# nokia-phone-arduino-shield.net
KiCad netlist of a schematic drawn in EAGLE
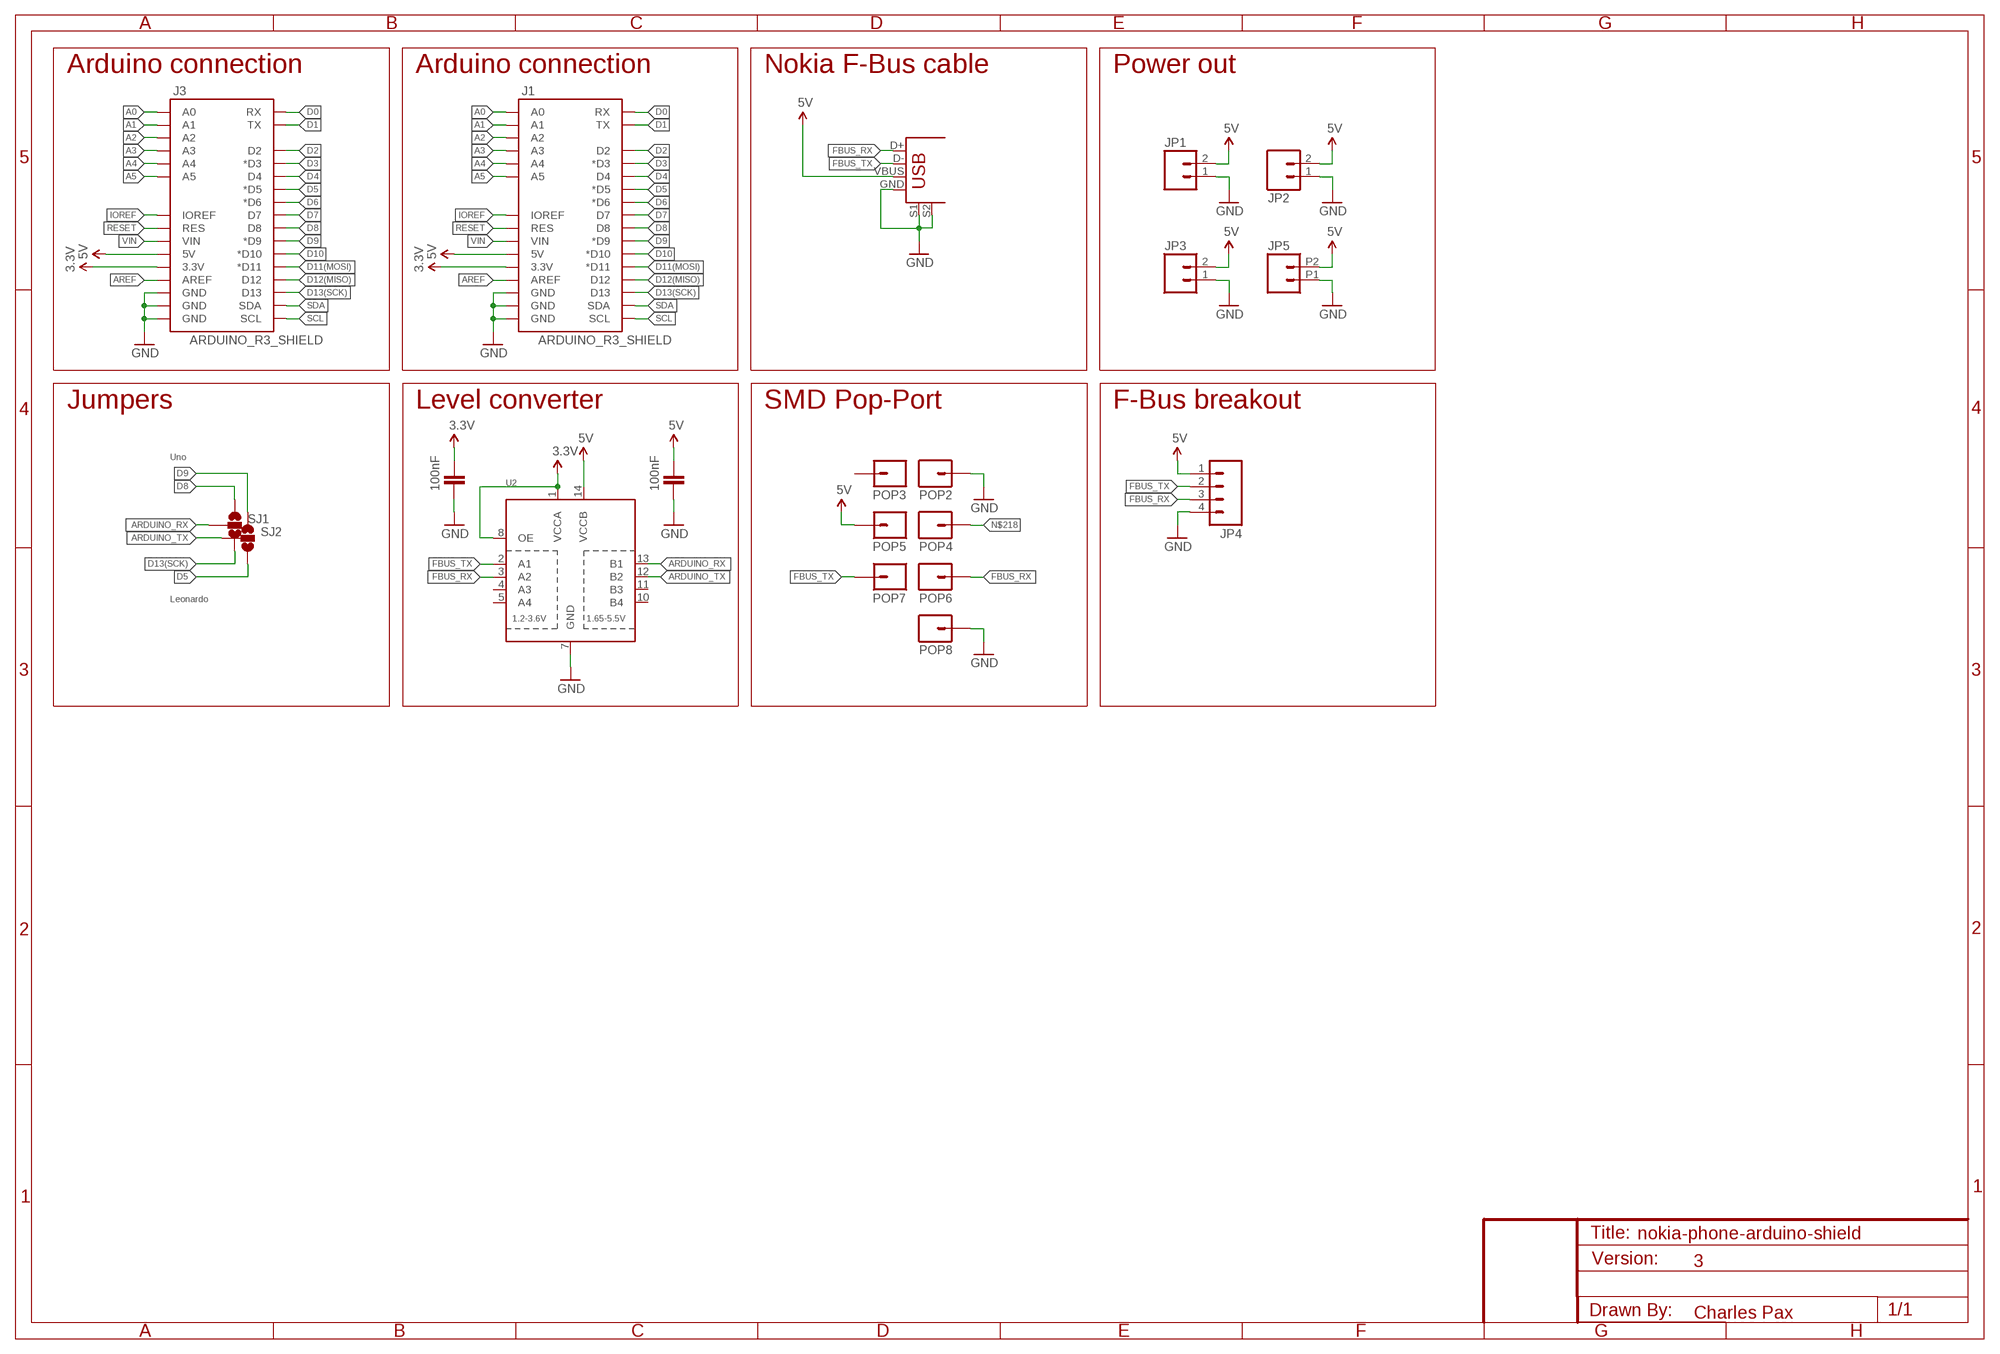
[diagram p0: schematic, sheet 1]

(export (version "E")
  (design (tool "Eeschema 10.0.6"))
  (components
    (comp (ref "C3")
      (value "100nF")
      (footprint "eagle-import:SPARKFUN-CAPACITORS_0603-CAP")
      (fields (field (name "MPN") "CL10B104KO8NNNC"))
      (libsource (lib "eagle-import") (part "SPARKFUN-CAPACITORS_CAP0603-CAP"))
    )
    (comp (ref "C4")
      (value "100nF")
      (footprint "eagle-import:SPARKFUN-CAPACITORS_0603-CAP")
      (fields (field (name "MPN") "CL10B104KO8NNNC"))
      (libsource (lib "eagle-import") (part "SPARKFUN-CAPACITORS_CAP0603-CAP"))
    )
    (comp (ref "J1")
      (value "ARDUINO_R3_SHIELD")
      (footprint "eagle-import:UNO_R3_SHIELD_NOLABELS_LOCK")
      (libsource (lib "eagle-import") (part "ARDUINO_R3_SHIELDUNO_R3_SHIELD_NOLABELS_LOCK"))
    )
    (comp (ref "J3")
      (value "ARDUINO_R3_SHIELD")
      (footprint "eagle-import:UNO_R3_SHIELD_NOLABELS_LOCK")
      (libsource (lib "eagle-import") (part "ARDUINO_R3_SHIELDUNO_R3_SHIELD_NOLABELS_LOCK"))
    )
    (comp (ref "JP1")
      (value "M02LOCK")
      (footprint "eagle-import:1X02_LOCK")
      (libsource (lib "eagle-import") (part "M02LOCK"))
    )
    (comp (ref "JP2")
      (value "M02-JST-2MM-SMT")
      (footprint "eagle-import:JST-2-SMD")
      (libsource (lib "eagle-import") (part "M02-JST-2MM-SMT"))
    )
    (comp (ref "JP3")
      (value "M02LOCK")
      (footprint "eagle-import:1X02_LOCK")
      (libsource (lib "eagle-import") (part "M02LOCK"))
    )
    (comp (ref "JP4")
      (value "M04LOCK")
      (footprint "eagle-import:1X04_LOCK")
      (libsource (lib "eagle-import") (part "M04LOCK"))
    )
    (comp (ref "JP5")
      (value "M022.54MM_SCREWTERM")
      (footprint "eagle-import:1X02_2.54_SCREWTERM")
      (libsource (lib "eagle-import") (part "M022.54MM_SCREWTERM"))
    )
    (comp (ref "POP2")
      (value "M01SMD-4.5X1.5")
      (footprint "eagle-import:PAD-1.5X4.5")
      (libsource (lib "eagle-import") (part "M01SMD-4.5X1.5"))
    )
    (comp (ref "POP3")
      (value "M01SMD-4.5X1.5")
      (footprint "eagle-import:PAD-1.5X4.5")
      (libsource (lib "eagle-import") (part "M01SMD-4.5X1.5"))
    )
    (comp (ref "POP4")
      (value "M01SMD-4.5X1.5")
      (footprint "eagle-import:PAD-1.5X4.5")
      (libsource (lib "eagle-import") (part "M01SMD-4.5X1.5"))
    )
    (comp (ref "POP5")
      (value "M01SMD-4.5X1.5")
      (footprint "eagle-import:PAD-1.5X4.5")
      (libsource (lib "eagle-import") (part "M01SMD-4.5X1.5"))
    )
    (comp (ref "POP6")
      (value "M01SMD-4.5X1.5")
      (footprint "eagle-import:PAD-1.5X4.5")
      (libsource (lib "eagle-import") (part "M01SMD-4.5X1.5"))
    )
    (comp (ref "POP7")
      (value "M01SMD-4.5X1.5")
      (footprint "eagle-import:PAD-1.5X4.5")
      (libsource (lib "eagle-import") (part "M01SMD-4.5X1.5"))
    )
    (comp (ref "POP8")
      (value "M01SMD-4.5X1.5")
      (footprint "eagle-import:PAD-1.5X4.5")
      (libsource (lib "eagle-import") (part "M01SMD-4.5X1.5"))
    )
    (comp (ref "SJ1")
      (value "SOLDERJUMPER_2WAYS")
      (footprint "eagle-import:SJ_3")
      (libsource (lib "eagle-import") (part "SOLDERJUMPER_2WAYS"))
    )
    (comp (ref "SJ2")
      (value "SOLDERJUMPER_2WAYS")
      (footprint "eagle-import:SJ_3")
      (libsource (lib "eagle-import") (part "SOLDERJUMPER_2WAYS"))
    )
    (comp (ref "U$2")
      (value "USB+SHIELDUSB-A-S-NOSILK-FEMALE")
      (footprint "eagle-import:USB-A-S-NOSILK-FEMALE")
      (libsource (lib "eagle-import") (part "USB+SHIELDUSB-A-S-NOSILK-FEMALE"))
    )
    (comp (ref "U2")
      (value "TXB0104PWRSOIC14")
      (footprint "eagle-import:SO14")
      (fields (field (name "MPN") "TXB0104DR"))
      (libsource (lib "eagle-import") (part "TXB0104PWRSOIC14"))
    )
  )
  (nets
    (net (code "1") (name "3.3V") (class "Default")
      (node (ref "C3") (pin "2") (pinfunction "2_2") (pintype "passive"))
      (node (ref "J1") (pin "3.3V") (pinfunction "3.3V_3.3V") (pintype "bidirectional"))
      (node (ref "J3") (pin "3.3V") (pinfunction "3.3V_3.3V") (pintype "bidirectional"))
      (node (ref "U2") (pin "1") (pinfunction "VCCA_1") (pintype "bidirectional"))
      (node (ref "U2") (pin "8") (pinfunction "OE_8") (pintype "bidirectional"))
    )
    (net (code "2") (name "5V") (class "Default")
      (node (ref "C4") (pin "2") (pinfunction "2_2") (pintype "passive"))
      (node (ref "J1") (pin "5V") (pinfunction "5V_5V") (pintype "bidirectional"))
      (node (ref "J3") (pin "5V") (pinfunction "5V_5V") (pintype "bidirectional"))
      (node (ref "JP1") (pin "2") (pinfunction "2_2") (pintype "passive"))
      (node (ref "JP2") (pin "2") (pinfunction "1_2") (pintype "passive"))
      (node (ref "JP3") (pin "2") (pinfunction "2_2") (pintype "passive"))
      (node (ref "JP4") (pin "1") (pinfunction "1_1") (pintype "passive"))
      (node (ref "JP5") (pin "P2") (pinfunction "2_P2") (pintype "passive"))
      (node (ref "POP5") (pin "P$1") (pinfunction "1_P$1") (pintype "passive"))
      (node (ref "U$2") (pin "VBUS") (pinfunction "VBUS_VBUS") (pintype "bidirectional"))
      (node (ref "U2") (pin "14") (pinfunction "VCCB_14") (pintype "bidirectional"))
    )
    (net (code "3") (name "A0") (class "Default")
      (node (ref "J1") (pin "A0") (pinfunction "A0_A0") (pintype "bidirectional"))
      (node (ref "J3") (pin "A0") (pinfunction "A0_A0") (pintype "bidirectional"))
    )
    (net (code "4") (name "A1") (class "Default")
      (node (ref "J1") (pin "A1") (pinfunction "A1_A1") (pintype "bidirectional"))
      (node (ref "J3") (pin "A1") (pinfunction "A1_A1") (pintype "bidirectional"))
    )
    (net (code "5") (name "A2") (class "Default")
      (node (ref "J1") (pin "A2") (pinfunction "A2_A2") (pintype "bidirectional"))
      (node (ref "J3") (pin "A2") (pinfunction "A2_A2") (pintype "bidirectional"))
    )
    (net (code "6") (name "A3") (class "Default")
      (node (ref "J1") (pin "A3") (pinfunction "A3_A3") (pintype "bidirectional"))
      (node (ref "J3") (pin "A3") (pinfunction "A3_A3") (pintype "bidirectional"))
    )
    (net (code "7") (name "A4") (class "Default")
      (node (ref "J1") (pin "A4") (pinfunction "A4_A4") (pintype "bidirectional"))
      (node (ref "J3") (pin "A4") (pinfunction "A4_A4") (pintype "bidirectional"))
    )
    (net (code "8") (name "A5") (class "Default")
      (node (ref "J1") (pin "A5") (pinfunction "A5_A5") (pintype "bidirectional"))
      (node (ref "J3") (pin "A5") (pinfunction "A5_A5") (pintype "bidirectional"))
    )
    (net (code "9") (name "ARDUINO_RX") (class "Default")
      (node (ref "SJ1") (pin "2") (pinfunction "2_2") (pintype "passive"))
      (node (ref "U2") (pin "13") (pinfunction "B1_13") (pintype "bidirectional"))
    )
    (net (code "10") (name "ARDUINO_TX") (class "Default")
      (node (ref "SJ2") (pin "2") (pinfunction "2_2") (pintype "passive"))
      (node (ref "U2") (pin "12") (pinfunction "B2_12") (pintype "bidirectional"))
    )
    (net (code "11") (name "AREF") (class "Default")
      (node (ref "J1") (pin "AREF") (pinfunction "AREF_AREF") (pintype "bidirectional"))
      (node (ref "J3") (pin "AREF") (pinfunction "AREF_AREF") (pintype "bidirectional"))
    )
    (net (code "12") (name "D0") (class "Default")
      (node (ref "J1") (pin "RX") (pinfunction "RX_RX") (pintype "bidirectional"))
      (node (ref "J3") (pin "RX") (pinfunction "RX_RX") (pintype "bidirectional"))
    )
    (net (code "13") (name "D1") (class "Default")
      (node (ref "J1") (pin "TX") (pinfunction "TX_TX") (pintype "bidirectional"))
      (node (ref "J3") (pin "TX") (pinfunction "TX_TX") (pintype "bidirectional"))
    )
    (net (code "14") (name "D2") (class "Default")
      (node (ref "J1") (pin "D2") (pinfunction "D2_D2") (pintype "bidirectional"))
      (node (ref "J3") (pin "D2") (pinfunction "D2_D2") (pintype "bidirectional"))
    )
    (net (code "15") (name "D3") (class "Default")
      (node (ref "J1") (pin "D3") (pinfunction "*D3_D3") (pintype "bidirectional"))
      (node (ref "J3") (pin "D3") (pinfunction "*D3_D3") (pintype "bidirectional"))
    )
    (net (code "16") (name "D4") (class "Default")
      (node (ref "J1") (pin "D4") (pinfunction "D4_D4") (pintype "bidirectional"))
      (node (ref "J3") (pin "D4") (pinfunction "D4_D4") (pintype "bidirectional"))
    )
    (net (code "17") (name "D5") (class "Default")
      (node (ref "J1") (pin "D5") (pinfunction "*D5_D5") (pintype "bidirectional"))
      (node (ref "J3") (pin "D5") (pinfunction "*D5_D5") (pintype "bidirectional"))
      (node (ref "SJ2") (pin "3") (pinfunction "3_3") (pintype "passive"))
    )
    (net (code "18") (name "D6") (class "Default")
      (node (ref "J1") (pin "D6") (pinfunction "*D6_D6") (pintype "bidirectional"))
      (node (ref "J3") (pin "D6") (pinfunction "*D6_D6") (pintype "bidirectional"))
    )
    (net (code "19") (name "D7") (class "Default")
      (node (ref "J1") (pin "D7") (pinfunction "D7_D7") (pintype "bidirectional"))
      (node (ref "J3") (pin "D7") (pinfunction "D7_D7") (pintype "bidirectional"))
    )
    (net (code "20") (name "D8") (class "Default")
      (node (ref "J1") (pin "D8") (pinfunction "D8_D8") (pintype "bidirectional"))
      (node (ref "J3") (pin "D8") (pinfunction "D8_D8") (pintype "bidirectional"))
      (node (ref "SJ1") (pin "1") (pinfunction "1_1") (pintype "passive"))
    )
    (net (code "21") (name "D9") (class "Default")
      (node (ref "J1") (pin "D9") (pinfunction "*D9_D9") (pintype "bidirectional"))
      (node (ref "J3") (pin "D9") (pinfunction "*D9_D9") (pintype "bidirectional"))
      (node (ref "SJ2") (pin "1") (pinfunction "1_1") (pintype "passive"))
    )
    (net (code "22") (name "D10") (class "Default")
      (node (ref "J1") (pin "D10") (pinfunction "*D10_D10") (pintype "bidirectional"))
      (node (ref "J3") (pin "D10") (pinfunction "*D10_D10") (pintype "bidirectional"))
    )
    (net (code "23") (name "D11(MOSI)") (class "Default")
      (node (ref "J1") (pin "D11") (pinfunction "*D11_D11") (pintype "bidirectional"))
      (node (ref "J3") (pin "D11") (pinfunction "*D11_D11") (pintype "bidirectional"))
    )
    (net (code "24") (name "D12(MISO)") (class "Default")
      (node (ref "J1") (pin "D12") (pinfunction "D12_D12") (pintype "bidirectional"))
      (node (ref "J3") (pin "D12") (pinfunction "D12_D12") (pintype "bidirectional"))
    )
    (net (code "25") (name "D13(SCK)") (class "Default")
      (node (ref "J1") (pin "D13") (pinfunction "D13_D13") (pintype "bidirectional"))
      (node (ref "J3") (pin "D13") (pinfunction "D13_D13") (pintype "bidirectional"))
      (node (ref "SJ1") (pin "3") (pinfunction "3_3") (pintype "passive"))
    )
    (net (code "26") (name "FBUS_RX") (class "Default")
      (node (ref "JP4") (pin "3") (pinfunction "3_3") (pintype "passive"))
      (node (ref "POP6") (pin "P$1") (pinfunction "1_P$1") (pintype "passive"))
      (node (ref "U$2") (pin "D+") (pinfunction "D+_D+") (pintype "bidirectional"))
      (node (ref "U2") (pin "3") (pinfunction "A2_3") (pintype "bidirectional"))
    )
    (net (code "27") (name "FBUS_TX") (class "Default")
      (node (ref "JP4") (pin "2") (pinfunction "2_2") (pintype "passive"))
      (node (ref "POP7") (pin "P$1") (pinfunction "1_P$1") (pintype "passive"))
      (node (ref "U$2") (pin "D-") (pinfunction "D-_D-") (pintype "bidirectional"))
      (node (ref "U2") (pin "2") (pinfunction "A1_2") (pintype "bidirectional"))
    )
    (net (code "28") (name "GND") (class "Default")
      (node (ref "C3") (pin "1") (pinfunction "1_1") (pintype "passive"))
      (node (ref "C4") (pin "1") (pinfunction "1_1") (pintype "passive"))
      (node (ref "J1") (pin "GND@0") (pinfunction "GND_GND@0") (pintype "bidirectional"))
      (node (ref "J1") (pin "GND@1") (pinfunction "GND_GND@1") (pintype "bidirectional"))
      (node (ref "J1") (pin "GND@2") (pinfunction "GND_GND@2") (pintype "bidirectional"))
      (node (ref "J3") (pin "GND@0") (pinfunction "GND_GND@0") (pintype "bidirectional"))
      (node (ref "J3") (pin "GND@1") (pinfunction "GND_GND@1") (pintype "bidirectional"))
      (node (ref "J3") (pin "GND@2") (pinfunction "GND_GND@2") (pintype "bidirectional"))
      (node (ref "JP1") (pin "1") (pinfunction "1_1") (pintype "passive"))
      (node (ref "JP2") (pin "1") (pinfunction "2_1") (pintype "passive"))
      (node (ref "JP3") (pin "1") (pinfunction "1_1") (pintype "passive"))
      (node (ref "JP4") (pin "4") (pinfunction "4_4") (pintype "passive"))
      (node (ref "JP5") (pin "P1") (pinfunction "1_P1") (pintype "passive"))
      (node (ref "POP2") (pin "P$1") (pinfunction "1_P$1") (pintype "passive"))
      (node (ref "POP8") (pin "P$1") (pinfunction "1_P$1") (pintype "passive"))
      (node (ref "U$2") (pin "GND") (pinfunction "GND_GND") (pintype "bidirectional"))
      (node (ref "U$2") (pin "S1") (pinfunction "S1_S1") (pintype "bidirectional"))
      (node (ref "U$2") (pin "S2") (pinfunction "S2_S2") (pintype "bidirectional"))
      (node (ref "U2") (pin "7") (pinfunction "GND_7") (pintype "bidirectional"))
    )
    (net (code "29") (name "IOREF") (class "Default")
      (node (ref "J1") (pin "IOREF") (pinfunction "IOREF_IOREF") (pintype "bidirectional"))
      (node (ref "J3") (pin "IOREF") (pinfunction "IOREF_IOREF") (pintype "bidirectional"))
    )
    (net (code "30") (name "N$218") (class "Default")
      (node (ref "POP4") (pin "P$1") (pinfunction "1_P$1") (pintype "passive"))
    )
    (net (code "31") (name "RESET") (class "Default")
      (node (ref "J1") (pin "RES") (pinfunction "RES_RES") (pintype "bidirectional"))
      (node (ref "J3") (pin "RES") (pinfunction "RES_RES") (pintype "bidirectional"))
    )
    (net (code "32") (name "SCL") (class "Default")
      (node (ref "J1") (pin "SCL") (pinfunction "SCL_SCL") (pintype "bidirectional"))
      (node (ref "J3") (pin "SCL") (pinfunction "SCL_SCL") (pintype "bidirectional"))
    )
    (net (code "33") (name "SDA") (class "Default")
      (node (ref "J1") (pin "SDA") (pinfunction "SDA_SDA") (pintype "bidirectional"))
      (node (ref "J3") (pin "SDA") (pinfunction "SDA_SDA") (pintype "bidirectional"))
    )
    (net (code "34") (name "VIN") (class "Default")
      (node (ref "J1") (pin "VIN") (pinfunction "VIN_VIN") (pintype "bidirectional"))
      (node (ref "J3") (pin "VIN") (pinfunction "VIN_VIN") (pintype "bidirectional"))
    )
    (net (code "35") (name "unconnected-(POP3-1-PadP$1)") (class "Default")
      (node (ref "POP3") (pin "P$1") (pinfunction "1_P$1") (pintype "passive"))
    )
    (net (code "36") (name "unconnected-(U2-A3-Pad4)") (class "Default")
      (node (ref "U2") (pin "4") (pinfunction "A3_4") (pintype "bidirectional"))
    )
    (net (code "37") (name "unconnected-(U2-A4-Pad5)") (class "Default")
      (node (ref "U2") (pin "5") (pinfunction "A4_5") (pintype "bidirectional"))
    )
    (net (code "38") (name "unconnected-(U2-B3-Pad11)") (class "Default")
      (node (ref "U2") (pin "11") (pinfunction "B3_11") (pintype "bidirectional"))
    )
    (net (code "39") (name "unconnected-(U2-B4-Pad10)") (class "Default")
      (node (ref "U2") (pin "10") (pinfunction "B4_10") (pintype "bidirectional"))
    )
  )
)
